# FMC_LPC.net
KiCad netlist of a schematic drawn in Altium Designer
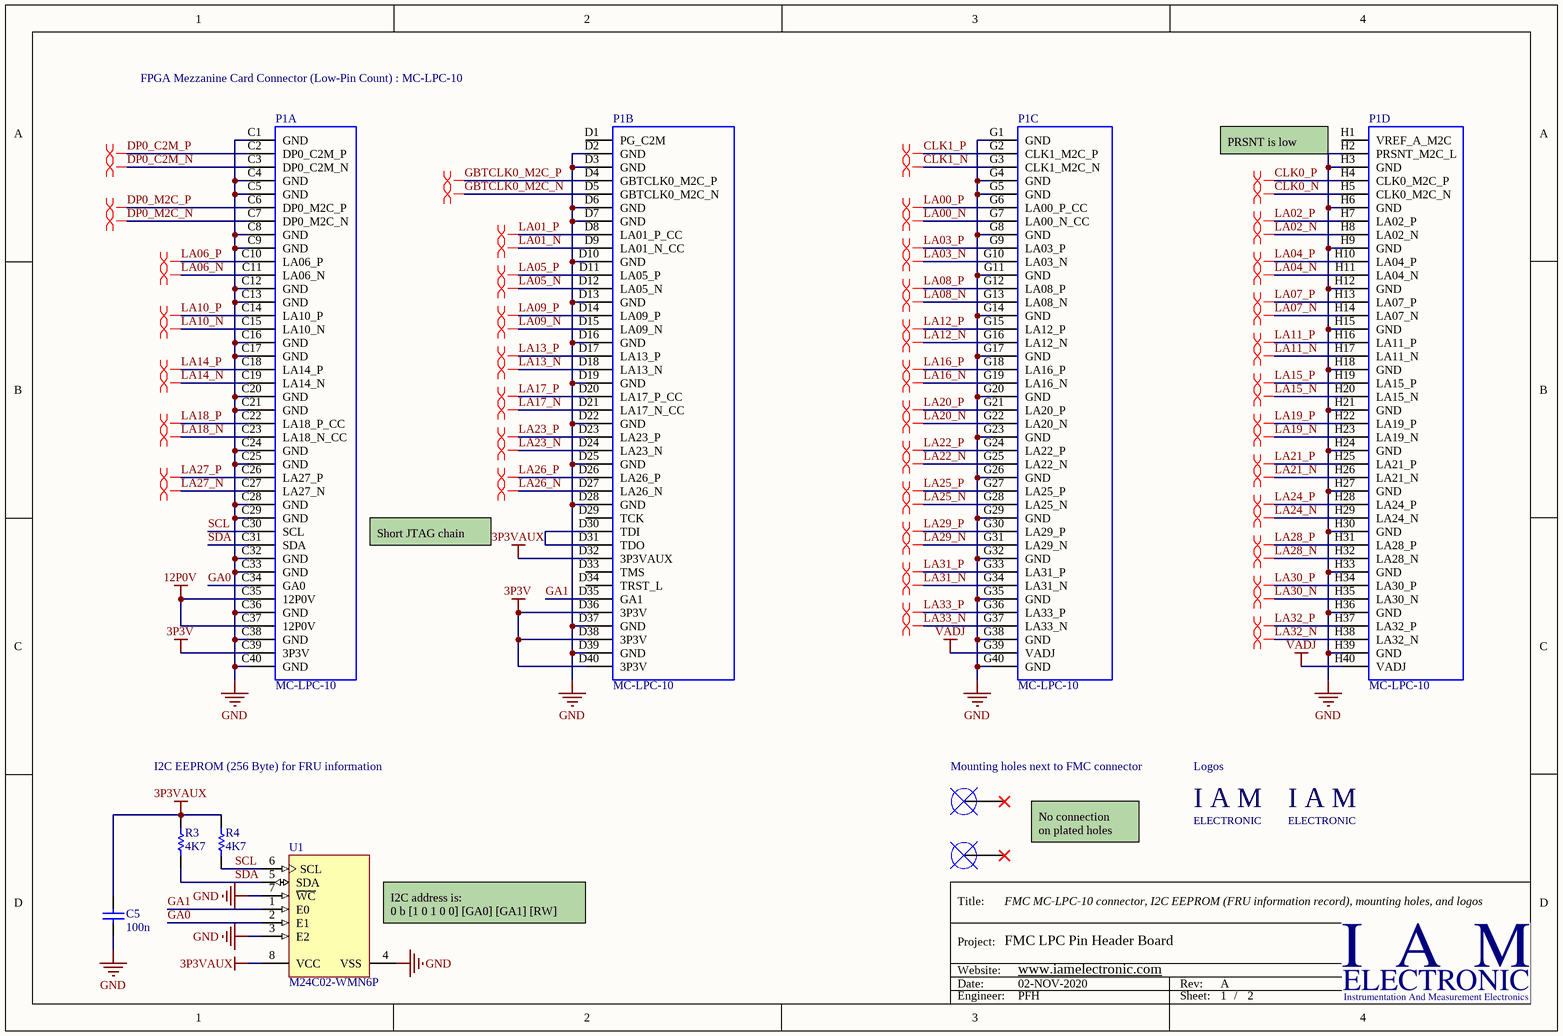
[diagram p0: FMC_LPC.SchDoc]

(export (version "E")
  (design (tool "Eeschema 10.0.6"))
  (components
    (comp (ref "C5")
      (value "100n")
      (footprint "CAPC1005X55X25ML05T10")
      (description "Chip Capacitor, 0.1 uF, +/- 10%, 16 V, -55 to 125 degC, 0402 (1005 Metric), RoHS, Tape and Reel")
      (fields (field (name "VOLTAGE") "16V") (field (name "TOLERANCE") "10%"))
      (libsource (lib "Altium Content Vault") (part "CAP-NP-2"))
    )
    (comp (ref "MHN")
      (value "2.7mm")
      (footprint "Mounting_Hole_Plated_2.7mm-COVERED")
      (description "Mounting hole, hole size 2.7mm")
      (libsource (lib "VITA_57_FMC") (part "Mounting_Hole_2.7mm"))
    )
    (comp (ref "MHS")
      (value "2.7mm")
      (footprint "Mounting_Hole_Plated_2.7mm-COVERED")
      (description "Mounting hole, hole size 2.7mm")
      (libsource (lib "VITA_57_FMC") (part "Mounting_Hole_2.7mm"))
    )
    (comp (ref "P1")
      (value "MC-LPC-10")
      (footprint "ASP-134604-01")
      (description "MC-LPC-10, FMC Low-pin count connector, lead free, 160 I/Os, male, 10 mm mated stack height")
      (fields (field (name "MANUFACTURER") "Samtec") (field (name "PART") "ASP-134604-01"))
      (libsource (lib "VITA_57_FMC") (part "MC-LPC-10"))
    )
    (comp (ref "R3")
      (value "4K7")
      (footprint "RESC1005X40X25ML05T05")
      (description "Chip Resistor, 4.7 KOhm, +/- 1%, 63 mW, -55 to 155 degC, 0402 (1005 Metric), RoHS, Tape and Reel")
      (fields (field (name "PARTNUMBER") "CRCW04024K70FKED") (field (name "TOLERANCE") "1%"))
      (libsource (lib "Altium Content Vault") (part "RES"))
    )
    (comp (ref "R4")
      (value "4K7")
      (footprint "RESC1005X40X25ML05T05")
      (description "Chip Resistor, 4.7 KOhm, +/- 1%, 63 mW, -55 to 155 degC, 0402 (1005 Metric), RoHS, Tape and Reel")
      (fields (field (name "PARTNUMBER") "CRCW04024K70FKED") (field (name "TOLERANCE") "1%"))
      (libsource (lib "Altium Content Vault") (part "RES"))
    )
    (comp (ref "STR1")
      (value "IAM LOGO")
      (footprint "IAM LOGO - SMALL - WWW")
      (description "I A M E L E C T R O N I C - Logo")
      (fields (field (name "MANUFACTURER") "IAM ELECTRONIC") (field (name "PART") "Logo"))
      (libsource (lib "IAM_LOGOS") (part "IAM_LOGO"))
    )
    (comp (ref "STR2")
      (value "IAM LOGO")
      (footprint "IAM LOGO - MEDIUM - WWW")
      (description "I A M E L E C T R O N I C - Logo")
      (fields (field (name "MANUFACTURER") "IAM ELECTRONIC") (field (name "PART") "Logo"))
      (libsource (lib "IAM_LOGOS") (part "IAM_LOGO"))
    )
    (comp (ref "U1")
      (value "M24C02-WMN6P")
      (footprint "STM-SO-8_D_L")
      (description "2-Kbit Serial I2C Bus EEPROM, 2.5 to 5.5 V, -40 to 85 degC, 8-Pin SOIC, RoHS, Tube")
      (fields (field (name "MANUFACTURER") "STMicroelectronics"))
      (libsource (lib "Altium Content Vault") (part "STM-M24C0X-X-8"))
    )
  )
  (nets
    (net (code "1") (name "/CLK0_N") (class "Default")
      (node (ref "P1") (pin "H5") (pinfunction "CLK0_M2C_N_H5") (pintype "passive"))
    )
    (net (code "2") (name "/CLK0_P") (class "Default")
      (node (ref "P1") (pin "H4") (pinfunction "CLK0_M2C_P_H4") (pintype "passive"))
    )
    (net (code "3") (name "/CLK1_N") (class "Default")
      (node (ref "P1") (pin "G3") (pinfunction "CLK1_M2C_N_G3") (pintype "passive"))
    )
    (net (code "4") (name "/CLK1_P") (class "Default")
      (node (ref "P1") (pin "G2") (pinfunction "CLK1_M2C_P_G2") (pintype "passive"))
    )
    (net (code "5") (name "/DP0_C2M_N") (class "Default")
      (node (ref "P1") (pin "C3") (pinfunction "DP0_C2M_N_C3") (pintype "passive"))
    )
    (net (code "6") (name "/DP0_C2M_P") (class "Default")
      (node (ref "P1") (pin "C2") (pinfunction "DP0_C2M_P_C2") (pintype "passive"))
    )
    (net (code "7") (name "/DP0_M2C_N") (class "Default")
      (node (ref "P1") (pin "C7") (pinfunction "DP0_M2C_N_C7") (pintype "passive"))
    )
    (net (code "8") (name "/DP0_M2C_P") (class "Default")
      (node (ref "P1") (pin "C6") (pinfunction "DP0_M2C_P_C6") (pintype "passive"))
    )
    (net (code "9") (name "/GA0") (class "Default")
      (node (ref "P1") (pin "C34") (pinfunction "GA0_C34") (pintype "passive"))
      (node (ref "U1") (pin "2") (pinfunction "E1_2") (pintype "input"))
    )
    (net (code "10") (name "/GA1") (class "Default")
      (node (ref "P1") (pin "D35") (pinfunction "GA1_D35") (pintype "passive"))
      (node (ref "U1") (pin "1") (pinfunction "E0_1") (pintype "input"))
    )
    (net (code "11") (name "/GBTCLK0_M2C_N") (class "Default")
      (node (ref "P1") (pin "D5") (pinfunction "GBTCLK0_M2C_N_D5") (pintype "passive"))
    )
    (net (code "12") (name "/GBTCLK0_M2C_P") (class "Default")
      (node (ref "P1") (pin "D4") (pinfunction "GBTCLK0_M2C_P_D4") (pintype "passive"))
    )
    (net (code "13") (name "/LA00_N") (class "Default")
      (node (ref "P1") (pin "G7") (pinfunction "LA00_N_CC_G7") (pintype "passive"))
    )
    (net (code "14") (name "/LA00_P") (class "Default")
      (node (ref "P1") (pin "G6") (pinfunction "LA00_P_CC_G6") (pintype "passive"))
    )
    (net (code "15") (name "/LA01_N") (class "Default")
      (node (ref "P1") (pin "D9") (pinfunction "LA01_N_CC_D9") (pintype "passive"))
    )
    (net (code "16") (name "/LA01_P") (class "Default")
      (node (ref "P1") (pin "D8") (pinfunction "LA01_P_CC_D8") (pintype "passive"))
    )
    (net (code "17") (name "/LA02_N") (class "Default")
      (node (ref "P1") (pin "H8") (pinfunction "LA02_N_H8") (pintype "passive"))
    )
    (net (code "18") (name "/LA02_P") (class "Default")
      (node (ref "P1") (pin "H7") (pinfunction "LA02_P_H7") (pintype "passive"))
    )
    (net (code "19") (name "/LA03_N") (class "Default")
      (node (ref "P1") (pin "G10") (pinfunction "LA03_N_G10") (pintype "passive"))
    )
    (net (code "20") (name "/LA03_P") (class "Default")
      (node (ref "P1") (pin "G9") (pinfunction "LA03_P_G9") (pintype "passive"))
    )
    (net (code "21") (name "/LA04_N") (class "Default")
      (node (ref "P1") (pin "H11") (pinfunction "LA04_N_H11") (pintype "passive"))
    )
    (net (code "22") (name "/LA04_P") (class "Default")
      (node (ref "P1") (pin "H10") (pinfunction "LA04_P_H10") (pintype "passive"))
    )
    (net (code "23") (name "/LA05_N") (class "Default")
      (node (ref "P1") (pin "D12") (pinfunction "LA05_N_D12") (pintype "passive"))
    )
    (net (code "24") (name "/LA05_P") (class "Default")
      (node (ref "P1") (pin "D11") (pinfunction "LA05_P_D11") (pintype "passive"))
    )
    (net (code "25") (name "/LA06_N") (class "Default")
      (node (ref "P1") (pin "C11") (pinfunction "LA06_N_C11") (pintype "passive"))
    )
    (net (code "26") (name "/LA06_P") (class "Default")
      (node (ref "P1") (pin "C10") (pinfunction "LA06_P_C10") (pintype "passive"))
    )
    (net (code "27") (name "/LA07_N") (class "Default")
      (node (ref "P1") (pin "H14") (pinfunction "LA07_N_H14") (pintype "passive"))
    )
    (net (code "28") (name "/LA07_P") (class "Default")
      (node (ref "P1") (pin "H13") (pinfunction "LA07_P_H13") (pintype "passive"))
    )
    (net (code "29") (name "/LA08_N") (class "Default")
      (node (ref "P1") (pin "G13") (pinfunction "LA08_N_G13") (pintype "passive"))
    )
    (net (code "30") (name "/LA08_P") (class "Default")
      (node (ref "P1") (pin "G12") (pinfunction "LA08_P_G12") (pintype "passive"))
    )
    (net (code "31") (name "/LA09_N") (class "Default")
      (node (ref "P1") (pin "D15") (pinfunction "LA09_N_D15") (pintype "passive"))
    )
    (net (code "32") (name "/LA09_P") (class "Default")
      (node (ref "P1") (pin "D14") (pinfunction "LA09_P_D14") (pintype "passive"))
    )
    (net (code "33") (name "/LA10_N") (class "Default")
      (node (ref "P1") (pin "C15") (pinfunction "LA10_N_C15") (pintype "passive"))
    )
    (net (code "34") (name "/LA10_P") (class "Default")
      (node (ref "P1") (pin "C14") (pinfunction "LA10_P_C14") (pintype "passive"))
    )
    (net (code "35") (name "/LA11_N") (class "Default")
      (node (ref "P1") (pin "H17") (pinfunction "LA11_N_H17") (pintype "passive"))
    )
    (net (code "36") (name "/LA11_P") (class "Default")
      (node (ref "P1") (pin "H16") (pinfunction "LA11_P_H16") (pintype "passive"))
    )
    (net (code "37") (name "/LA12_N") (class "Default")
      (node (ref "P1") (pin "G16") (pinfunction "LA12_N_G16") (pintype "passive"))
    )
    (net (code "38") (name "/LA12_P") (class "Default")
      (node (ref "P1") (pin "G15") (pinfunction "LA12_P_G15") (pintype "passive"))
    )
    (net (code "39") (name "/LA13_N") (class "Default")
      (node (ref "P1") (pin "D18") (pinfunction "LA13_N_D18") (pintype "passive"))
    )
    (net (code "40") (name "/LA13_P") (class "Default")
      (node (ref "P1") (pin "D17") (pinfunction "LA13_P_D17") (pintype "passive"))
    )
    (net (code "41") (name "/LA14_N") (class "Default")
      (node (ref "P1") (pin "C19") (pinfunction "LA14_N_C19") (pintype "passive"))
    )
    (net (code "42") (name "/LA14_P") (class "Default")
      (node (ref "P1") (pin "C18") (pinfunction "LA14_P_C18") (pintype "passive"))
    )
    (net (code "43") (name "/LA15_N") (class "Default")
      (node (ref "P1") (pin "H20") (pinfunction "LA15_N_H20") (pintype "passive"))
    )
    (net (code "44") (name "/LA15_P") (class "Default")
      (node (ref "P1") (pin "H19") (pinfunction "LA15_P_H19") (pintype "passive"))
    )
    (net (code "45") (name "/LA16_N") (class "Default")
      (node (ref "P1") (pin "G19") (pinfunction "LA16_N_G19") (pintype "passive"))
    )
    (net (code "46") (name "/LA16_P") (class "Default")
      (node (ref "P1") (pin "G18") (pinfunction "LA16_P_G18") (pintype "passive"))
    )
    (net (code "47") (name "/LA17_N") (class "Default")
      (node (ref "P1") (pin "D21") (pinfunction "LA17_N_CC_D21") (pintype "passive"))
    )
    (net (code "48") (name "/LA17_P") (class "Default")
      (node (ref "P1") (pin "D20") (pinfunction "LA17_P_CC_D20") (pintype "passive"))
    )
    (net (code "49") (name "/LA18_N") (class "Default")
      (node (ref "P1") (pin "C23") (pinfunction "LA18_N_CC_C23") (pintype "passive"))
    )
    (net (code "50") (name "/LA18_P") (class "Default")
      (node (ref "P1") (pin "C22") (pinfunction "LA18_P_CC_C22") (pintype "passive"))
    )
    (net (code "51") (name "/LA19_N") (class "Default")
      (node (ref "P1") (pin "H23") (pinfunction "LA19_N_H23") (pintype "passive"))
    )
    (net (code "52") (name "/LA19_P") (class "Default")
      (node (ref "P1") (pin "H22") (pinfunction "LA19_P_H22") (pintype "passive"))
    )
    (net (code "53") (name "/LA20_N") (class "Default")
      (node (ref "P1") (pin "G22") (pinfunction "LA20_N_G22") (pintype "passive"))
    )
    (net (code "54") (name "/LA20_P") (class "Default")
      (node (ref "P1") (pin "G21") (pinfunction "LA20_P_G21") (pintype "passive"))
    )
    (net (code "55") (name "/LA21_N") (class "Default")
      (node (ref "P1") (pin "H26") (pinfunction "LA21_N_H26") (pintype "passive"))
    )
    (net (code "56") (name "/LA21_P") (class "Default")
      (node (ref "P1") (pin "H25") (pinfunction "LA21_P_H25") (pintype "passive"))
    )
    (net (code "57") (name "/LA22_N") (class "Default")
      (node (ref "P1") (pin "G25") (pinfunction "LA22_N_G25") (pintype "passive"))
    )
    (net (code "58") (name "/LA22_P") (class "Default")
      (node (ref "P1") (pin "G24") (pinfunction "LA22_P_G24") (pintype "passive"))
    )
    (net (code "59") (name "/LA23_N") (class "Default")
      (node (ref "P1") (pin "D24") (pinfunction "LA23_N_D24") (pintype "passive"))
    )
    (net (code "60") (name "/LA23_P") (class "Default")
      (node (ref "P1") (pin "D23") (pinfunction "LA23_P_D23") (pintype "passive"))
    )
    (net (code "61") (name "/LA24_N") (class "Default")
      (node (ref "P1") (pin "H29") (pinfunction "LA24_N_H29") (pintype "passive"))
    )
    (net (code "62") (name "/LA24_P") (class "Default")
      (node (ref "P1") (pin "H28") (pinfunction "LA24_P_H28") (pintype "passive"))
    )
    (net (code "63") (name "/LA25_N") (class "Default")
      (node (ref "P1") (pin "G28") (pinfunction "LA25_N_G28") (pintype "passive"))
    )
    (net (code "64") (name "/LA25_P") (class "Default")
      (node (ref "P1") (pin "G27") (pinfunction "LA25_P_G27") (pintype "passive"))
    )
    (net (code "65") (name "/LA26_N") (class "Default")
      (node (ref "P1") (pin "D27") (pinfunction "LA26_N_D27") (pintype "passive"))
    )
    (net (code "66") (name "/LA26_P") (class "Default")
      (node (ref "P1") (pin "D26") (pinfunction "LA26_P_D26") (pintype "passive"))
    )
    (net (code "67") (name "/LA27_N") (class "Default")
      (node (ref "P1") (pin "C27") (pinfunction "LA27_N_C27") (pintype "passive"))
    )
    (net (code "68") (name "/LA27_P") (class "Default")
      (node (ref "P1") (pin "C26") (pinfunction "LA27_P_C26") (pintype "passive"))
    )
    (net (code "69") (name "/LA28_N") (class "Default")
      (node (ref "P1") (pin "H32") (pinfunction "LA28_N_H32") (pintype "passive"))
    )
    (net (code "70") (name "/LA28_P") (class "Default")
      (node (ref "P1") (pin "H31") (pinfunction "LA28_P_H31") (pintype "passive"))
    )
    (net (code "71") (name "/LA29_N") (class "Default")
      (node (ref "P1") (pin "G31") (pinfunction "LA29_N_G31") (pintype "passive"))
    )
    (net (code "72") (name "/LA29_P") (class "Default")
      (node (ref "P1") (pin "G30") (pinfunction "LA29_P_G30") (pintype "passive"))
    )
    (net (code "73") (name "/LA30_N") (class "Default")
      (node (ref "P1") (pin "H35") (pinfunction "LA30_N_H35") (pintype "passive"))
    )
    (net (code "74") (name "/LA30_P") (class "Default")
      (node (ref "P1") (pin "H34") (pinfunction "LA30_P_H34") (pintype "passive"))
    )
    (net (code "75") (name "/LA31_N") (class "Default")
      (node (ref "P1") (pin "G34") (pinfunction "LA31_N_G34") (pintype "passive"))
    )
    (net (code "76") (name "/LA31_P") (class "Default")
      (node (ref "P1") (pin "G33") (pinfunction "LA31_P_G33") (pintype "passive"))
    )
    (net (code "77") (name "/LA32_N") (class "Default")
      (node (ref "P1") (pin "H38") (pinfunction "LA32_N_H38") (pintype "passive"))
    )
    (net (code "78") (name "/LA32_P") (class "Default")
      (node (ref "P1") (pin "H37") (pinfunction "LA32_P_H37") (pintype "passive"))
    )
    (net (code "79") (name "/LA33_N") (class "Default")
      (node (ref "P1") (pin "G37") (pinfunction "LA33_N_G37") (pintype "passive"))
    )
    (net (code "80") (name "/LA33_P") (class "Default")
      (node (ref "P1") (pin "G36") (pinfunction "LA33_P_G36") (pintype "passive"))
    )
    (net (code "81") (name "/SCL") (class "Default")
      (node (ref "P1") (pin "C30") (pinfunction "SCL_C30") (pintype "passive"))
      (node (ref "R4") (pin "1") (pinfunction "1_1") (pintype "passive"))
      (node (ref "U1") (pin "6") (pinfunction "SCL_6") (pintype "input"))
    )
    (net (code "82") (name "/SDA") (class "Default")
      (node (ref "P1") (pin "C31") (pinfunction "SDA_C31") (pintype "passive"))
      (node (ref "R3") (pin "1") (pinfunction "1_1") (pintype "passive"))
      (node (ref "U1") (pin "5") (pinfunction "SDA_5") (pintype "bidirectional"))
    )
    (net (code "83") (name "3P3V") (class "Default")
      (node (ref "P1") (pin "C39") (pinfunction "3P3V_C39") (pintype "passive"))
      (node (ref "P1") (pin "D36") (pinfunction "3P3V_D36") (pintype "passive"))
      (node (ref "P1") (pin "D38") (pinfunction "3P3V_D38") (pintype "passive"))
      (node (ref "P1") (pin "D40") (pinfunction "3P3V_D40") (pintype "passive"))
    )
    (net (code "84") (name "3P3VAUX") (class "Default")
      (node (ref "C5") (pin "2") (pinfunction "2_2") (pintype "passive"))
      (node (ref "P1") (pin "D32") (pinfunction "3P3VAUX_D32") (pintype "passive"))
      (node (ref "R3") (pin "2") (pinfunction "2_2") (pintype "passive"))
      (node (ref "R4") (pin "2") (pinfunction "2_2") (pintype "passive"))
      (node (ref "U1") (pin "8") (pinfunction "VCC_8") (pintype "power_in"))
    )
    (net (code "85") (name "12P0V") (class "Default")
      (node (ref "P1") (pin "C35") (pinfunction "12P0V_C35") (pintype "passive"))
      (node (ref "P1") (pin "C37") (pinfunction "12P0V_C37") (pintype "passive"))
    )
    (net (code "86") (name "GND") (class "Default")
      (node (ref "C5") (pin "1") (pinfunction "1_1") (pintype "passive"))
      (node (ref "P1") (pin "C1") (pinfunction "GND_C1") (pintype "passive"))
      (node (ref "P1") (pin "C12") (pinfunction "GND_C12") (pintype "passive"))
      (node (ref "P1") (pin "C13") (pinfunction "GND_C13") (pintype "passive"))
      (node (ref "P1") (pin "C16") (pinfunction "GND_C16") (pintype "passive"))
      (node (ref "P1") (pin "C17") (pinfunction "GND_C17") (pintype "passive"))
      (node (ref "P1") (pin "C20") (pinfunction "GND_C20") (pintype "passive"))
      (node (ref "P1") (pin "C21") (pinfunction "GND_C21") (pintype "passive"))
      (node (ref "P1") (pin "C24") (pinfunction "GND_C24") (pintype "passive"))
      (node (ref "P1") (pin "C25") (pinfunction "GND_C25") (pintype "passive"))
      (node (ref "P1") (pin "C28") (pinfunction "GND_C28") (pintype "passive"))
      (node (ref "P1") (pin "C29") (pinfunction "GND_C29") (pintype "passive"))
      (node (ref "P1") (pin "C32") (pinfunction "GND_C32") (pintype "passive"))
      (node (ref "P1") (pin "C33") (pinfunction "GND_C33") (pintype "passive"))
      (node (ref "P1") (pin "C36") (pinfunction "GND_C36") (pintype "passive"))
      (node (ref "P1") (pin "C38") (pinfunction "GND_C38") (pintype "passive"))
      (node (ref "P1") (pin "C4") (pinfunction "GND_C4") (pintype "passive"))
      (node (ref "P1") (pin "C40") (pinfunction "GND_C40") (pintype "passive"))
      (node (ref "P1") (pin "C5") (pinfunction "GND_C5") (pintype "passive"))
      (node (ref "P1") (pin "C8") (pinfunction "GND_C8") (pintype "passive"))
      (node (ref "P1") (pin "C9") (pinfunction "GND_C9") (pintype "passive"))
      (node (ref "P1") (pin "D10") (pinfunction "GND_D10") (pintype "passive"))
      (node (ref "P1") (pin "D13") (pinfunction "GND_D13") (pintype "passive"))
      (node (ref "P1") (pin "D16") (pinfunction "GND_D16") (pintype "passive"))
      (node (ref "P1") (pin "D19") (pinfunction "GND_D19") (pintype "passive"))
      (node (ref "P1") (pin "D2") (pinfunction "GND_D2") (pintype "passive"))
      (node (ref "P1") (pin "D22") (pinfunction "GND_D22") (pintype "passive"))
      (node (ref "P1") (pin "D25") (pinfunction "GND_D25") (pintype "passive"))
      (node (ref "P1") (pin "D28") (pinfunction "GND_D28") (pintype "passive"))
      (node (ref "P1") (pin "D3") (pinfunction "GND_D3") (pintype "passive"))
      (node (ref "P1") (pin "D37") (pinfunction "GND_D37") (pintype "passive"))
      (node (ref "P1") (pin "D39") (pinfunction "GND_D39") (pintype "passive"))
      (node (ref "P1") (pin "D6") (pinfunction "GND_D6") (pintype "passive"))
      (node (ref "P1") (pin "D7") (pinfunction "GND_D7") (pintype "passive"))
      (node (ref "P1") (pin "G1") (pinfunction "GND_G1") (pintype "passive"))
      (node (ref "P1") (pin "G11") (pinfunction "GND_G11") (pintype "passive"))
      (node (ref "P1") (pin "G14") (pinfunction "GND_G14") (pintype "passive"))
      (node (ref "P1") (pin "G17") (pinfunction "GND_G17") (pintype "passive"))
      (node (ref "P1") (pin "G20") (pinfunction "GND_G20") (pintype "passive"))
      (node (ref "P1") (pin "G23") (pinfunction "GND_G23") (pintype "passive"))
      (node (ref "P1") (pin "G26") (pinfunction "GND_G26") (pintype "passive"))
      (node (ref "P1") (pin "G29") (pinfunction "GND_G29") (pintype "passive"))
      (node (ref "P1") (pin "G32") (pinfunction "GND_G32") (pintype "passive"))
      (node (ref "P1") (pin "G35") (pinfunction "GND_G35") (pintype "passive"))
      (node (ref "P1") (pin "G38") (pinfunction "GND_G38") (pintype "passive"))
      (node (ref "P1") (pin "G4") (pinfunction "GND_G4") (pintype "passive"))
      (node (ref "P1") (pin "G40") (pinfunction "GND_G40") (pintype "passive"))
      (node (ref "P1") (pin "G5") (pinfunction "GND_G5") (pintype "passive"))
      (node (ref "P1") (pin "G8") (pinfunction "GND_G8") (pintype "passive"))
      (node (ref "P1") (pin "H12") (pinfunction "GND_H12") (pintype "passive"))
      (node (ref "P1") (pin "H15") (pinfunction "GND_H15") (pintype "passive"))
      (node (ref "P1") (pin "H18") (pinfunction "GND_H18") (pintype "passive"))
      (node (ref "P1") (pin "H2") (pinfunction "PRSNT_M2C_L_H2") (pintype "passive"))
      (node (ref "P1") (pin "H21") (pinfunction "GND_H21") (pintype "passive"))
      (node (ref "P1") (pin "H24") (pinfunction "GND_H24") (pintype "passive"))
      (node (ref "P1") (pin "H27") (pinfunction "GND_H27") (pintype "passive"))
      (node (ref "P1") (pin "H3") (pinfunction "GND_H3") (pintype "passive"))
      (node (ref "P1") (pin "H30") (pinfunction "GND_H30") (pintype "passive"))
      (node (ref "P1") (pin "H33") (pinfunction "GND_H33") (pintype "passive"))
      (node (ref "P1") (pin "H36") (pinfunction "GND_H36") (pintype "passive"))
      (node (ref "P1") (pin "H39") (pinfunction "GND_H39") (pintype "passive"))
      (node (ref "P1") (pin "H6") (pinfunction "GND_H6") (pintype "passive"))
      (node (ref "P1") (pin "H9") (pinfunction "GND_H9") (pintype "passive"))
      (node (ref "U1") (pin "3") (pinfunction "E2_3") (pintype "input"))
      (node (ref "U1") (pin "4") (pinfunction "VSS_4") (pintype "power_in"))
      (node (ref "U1") (pin "7") (pinfunction "~{WC}_7") (pintype "input"))
    )
    (net (code "87") (name "Net-(P1B-TDI)") (class "Default")
      (node (ref "P1") (pin "D30") (pinfunction "TDI_D30") (pintype "passive"))
      (node (ref "P1") (pin "D31") (pinfunction "TDO_D31") (pintype "passive"))
    )
    (net (code "88") (name "VADJ") (class "Default")
      (node (ref "P1") (pin "G39") (pinfunction "VADJ_G39") (pintype "passive"))
      (node (ref "P1") (pin "H40") (pinfunction "VADJ_H40") (pintype "passive"))
    )
    (net (code "89") (name "unconnected-(MHN-Pad0)") (class "Default")
      (node (ref "MHN") (pin "0") (pinfunction "0_0") (pintype "passive+no_connect"))
    )
    (net (code "90") (name "unconnected-(MHS-Pad0)") (class "Default")
      (node (ref "MHS") (pin "0") (pinfunction "0_0") (pintype "passive+no_connect"))
    )
    (net (code "91") (name "unconnected-(P1B-PG_C2M-PadD1)") (class "Default")
      (node (ref "P1") (pin "D1") (pinfunction "PG_C2M_D1") (pintype "passive"))
    )
    (net (code "92") (name "unconnected-(P1B-TCK-PadD29)") (class "Default")
      (node (ref "P1") (pin "D29") (pinfunction "TCK_D29") (pintype "passive"))
    )
    (net (code "93") (name "unconnected-(P1B-TMS-PadD33)") (class "Default")
      (node (ref "P1") (pin "D33") (pinfunction "TMS_D33") (pintype "passive"))
    )
    (net (code "94") (name "unconnected-(P1B-TRST_L-PadD34)") (class "Default")
      (node (ref "P1") (pin "D34") (pinfunction "TRST_L_D34") (pintype "passive"))
    )
    (net (code "95") (name "unconnected-(P1D-VREF_A_M2C-PadH1)") (class "Default")
      (node (ref "P1") (pin "H1") (pinfunction "VREF_A_M2C_H1") (pintype "passive"))
    )
  )
)
